# USB_Type-C_Port_V2_0.net
KiCad netlist of a schematic drawn in Altium Designer
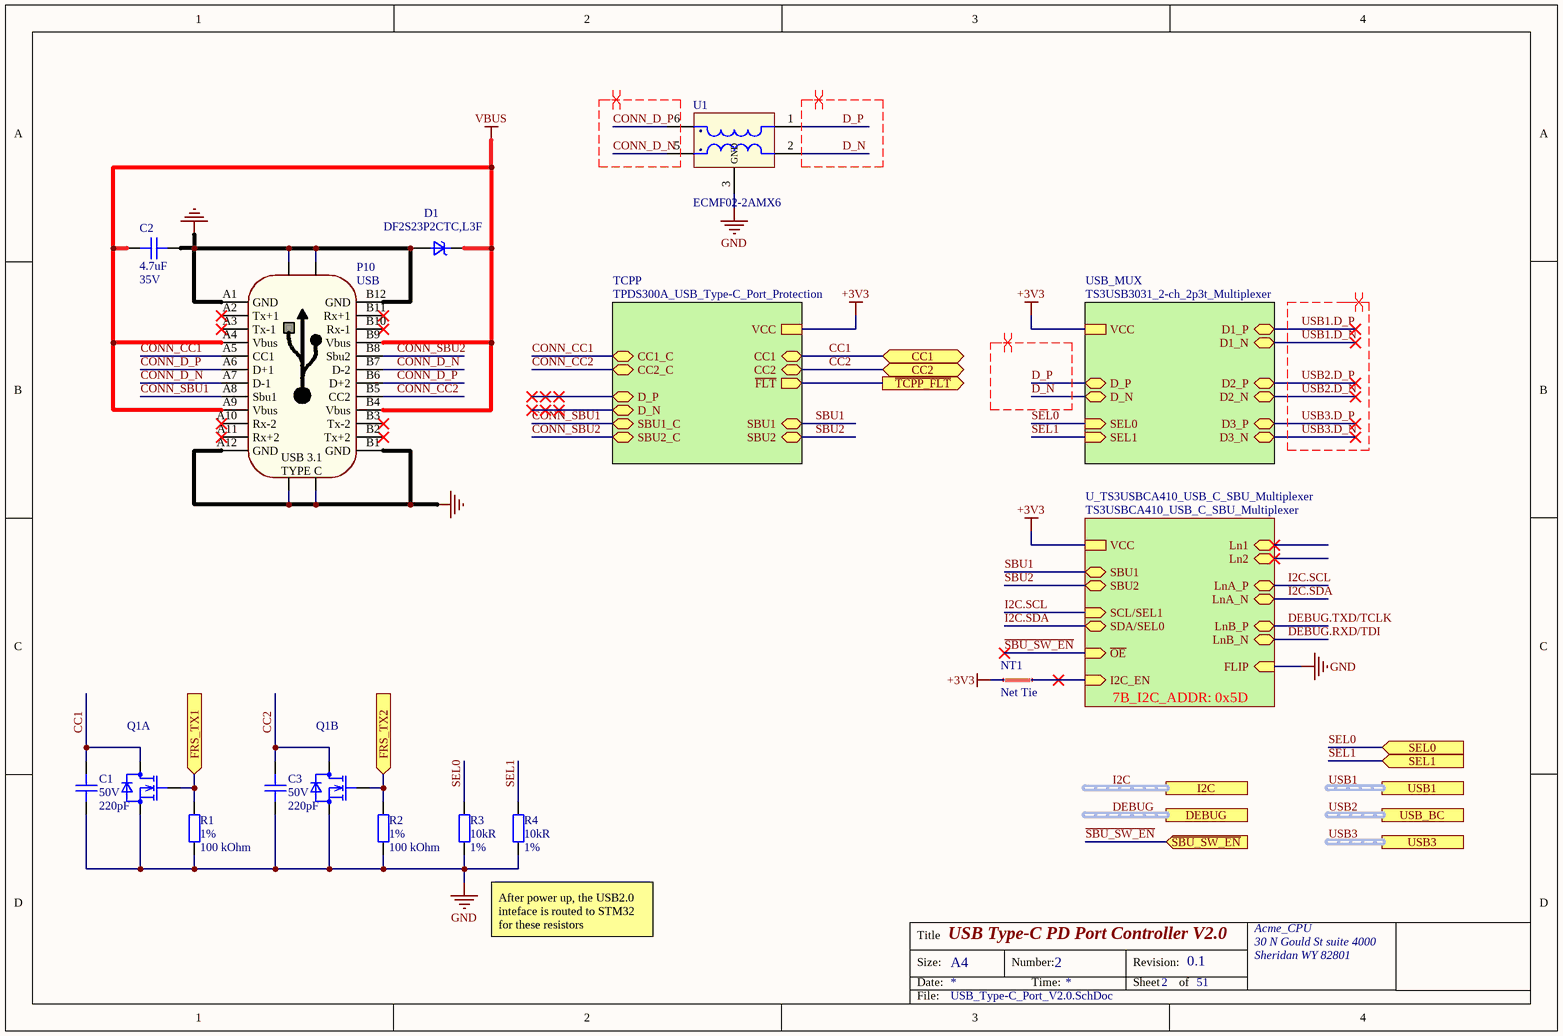
[diagram p0: USB_Type-C_Port_V2.0.SchDoc]

(export (version "E")
  (design (tool "Eeschema 10.0.6"))
  (components
    (comp (ref "C1")
      (value "CAP CER 220PF 50V X7R 0402")
      (footprint "C0402")
      (description "220pF ±10% 50V Ceramic Capacitor X7R 0402 (1005 Metric)")
      (fields
        (field (name "MANUFACTURER") "Yageo")
        (field (name "MANUFACTURER PART NUMBER") "CC0402KRX7R9BB221")
        (field (name "VOLTAGE RATING") "50V")
        (field (name "CAPACITANCE") "220pF")
      )
      (libsource (lib "capacitors_smd") (part "CAP CER 220PF 50V X7R 0402"))
    )
    (comp (ref "C2")
      (value "CAP CER 4.7UF 35V X7R 0805")
      (footprint "C0805")
      (fields
        (field (name "MANUFACTURER") "TDK")
        (field (name "MANUFACTURER PART NUMBER") "C2012X7R1V475K125AC")
        (field (name "TOLERANCE") "10%")
        (field (name "CAPACITANCE") "4.7uF")
        (field (name "VOLTAGE RATING") "35V")
      )
      (libsource (lib "capacitors_smd") (part "CAP CER 4.7UF 35V X7R 0805"))
    )
    (comp (ref "C3")
      (value "CAP CER 220PF 50V X7R 0402")
      (footprint "C0402")
      (description "220pF ±10% 50V Ceramic Capacitor X7R 0402 (1005 Metric)")
      (fields
        (field (name "MANUFACTURER") "Yageo")
        (field (name "MANUFACTURER PART NUMBER") "CC0402KRX7R9BB221")
        (field (name "VOLTAGE RATING") "50V")
        (field (name "CAPACITANCE") "220pF")
      )
      (libsource (lib "capacitors_smd") (part "CAP CER 220PF 50V X7R 0402"))
    )
    (comp (ref "D1")
      (value "DF2S23P2CTC,L3F")
      (footprint "CST2C")
      (description "35.7V Clamp 14A (8/20µs) Ipp Tvs Diode Surface Mount CST2C")
      (fields (field (name "MANUFACTURER") "Toshiba Semiconductor and Storage"))
      (libsource (lib "Control_Board_Model") (part "TVS DIODE 21VWM 35.7VC CST2C"))
    )
    (comp (ref "NT1")
      (value "Net Tie")
      (footprint "Net Tie 6x30mil")
      (libsource (lib "BLDC_Motor_Driver") (part "Net Tie Line"))
    )
    (comp (ref "P10")
      (value "USB")
      (footprint "MOLEX_2012670005")
      (fields (field (name "MANUFACTURER") "Molex") (field (name "MANUFACTURER PART NUMBER") "201267-0005"))
      (libsource (lib "connectors_usb") (part "CONN 2012670005 RCP USB3.1 TYPEC 24P SMD RA"))
    )
    (comp (ref "Q1")
      (value "DMN32D2LV-7")
      (footprint "SON_400UV-7_DIO")
      (description "Mosfet Array 2 N-Channel (Dual) 30V 400mA 400mW Surface Mount SOT-563")
      (fields (field (name "MANUFACTURER") "Diodes"))
      (libsource (lib "mosfets") (part "ARRAY MOSFET 2N-CH 30V 0.4A SOT-563"))
    )
    (comp (ref "R1")
      (value "RES SMD 100K OHM 1% 1/16W 0402")
      (footprint "R0402")
      (description "100 kOhms ±1% 0.063W, 1/16W Chip Resistor 0402 (1005 Metric) Moisture Resistant Thick Film")
      (fields
        (field (name "MANUFACTURER") "Yageo")
        (field (name "MANUFACTURER PART NUMBER") "RC0402FR-07100KL")
        (field (name "TOLERANCE") "1%")
        (field (name "RESISTANCE") "100 kOhm")
      )
      (libsource (lib "resistors_smd") (part "RES SMD 100K OHM 1% 1/16W 0402"))
    )
    (comp (ref "R2")
      (value "RES SMD 100K OHM 1% 1/16W 0402")
      (footprint "R0402")
      (description "100 kOhms ±1% 0.063W, 1/16W Chip Resistor 0402 (1005 Metric) Moisture Resistant Thick Film")
      (fields
        (field (name "MANUFACTURER") "Yageo")
        (field (name "MANUFACTURER PART NUMBER") "RC0402FR-07100KL")
        (field (name "TOLERANCE") "1%")
        (field (name "RESISTANCE") "100 kOhm")
      )
      (libsource (lib "resistors_smd") (part "RES SMD 100K OHM 1% 1/16W 0402"))
    )
    (comp (ref "R3")
      (value "RES SMD 10K OHM 1% 1/16W 0402")
      (footprint "R0402")
      (description "10 kOhms ±1% 0.063W, 1/16W Chip Resistor 0402 (1005 Metric) Moisture Resistant Thick Film")
      (fields
        (field (name "MANUFACTURER") "Yageo")
        (field (name "MANUFACTURER PART NUMBER") "RC0402FR-0710KP")
        (field (name "RESISTANCE") "10kR")
        (field (name "TOLERANCE") "1%")
      )
      (libsource (lib "resistors_smd") (part "RES SMD 10K OHM 1% 1/16W 0402"))
    )
    (comp (ref "R4")
      (value "RES SMD 10K OHM 1% 1/16W 0402")
      (footprint "R0402")
      (description "10 kOhms ±1% 0.063W, 1/16W Chip Resistor 0402 (1005 Metric) Moisture Resistant Thick Film")
      (fields
        (field (name "MANUFACTURER") "Yageo")
        (field (name "MANUFACTURER PART NUMBER") "RC0402FR-0710KP")
        (field (name "RESISTANCE") "10kR")
        (field (name "TOLERANCE") "1%")
      )
      (libsource (lib "resistors_smd") (part "RES SMD 10K OHM 1% 1/16W 0402"))
    )
    (comp (ref "U1")
      (value "ECMF02-2AMX6")
      (footprint "QFN-6L")
      (description "2 Line Common Mode Choke Surface Mount  200mA DCR 2.5Ohm")
      (fields (field (name "MANUFACTURER") "STMicroelectronics"))
      (libsource (lib "diodes_tvs") (part "CMC 200MA 2LN SMD ESD"))
    )
  )
  (nets
    (net (code "6") (name "+3V3") (class "Default") (node (ref "NT1") (pin "1") (pintype "passive")))
    (net (code "7") (name "/CC1") (class "Default")
      (node (ref "C1") (pin "2") (pinfunction "2_2") (pintype "passive"))
      (node (ref "Q1") (pin "6") (pinfunction "D_6") (pintype "passive"))
    )
    (net (code "8") (name "/CC2") (class "Default")
      (node (ref "C3") (pin "2") (pinfunction "2_2") (pintype "passive"))
      (node (ref "Q1") (pin "3") (pinfunction "D_3") (pintype "passive"))
    )
    (net (code "9") (name "/CONN_CC1") (class "Default")
      (node (ref "P10") (pin "A5") (pinfunction "CC1_A5") (pintype "passive"))
    )
    (net (code "10") (name "/CONN_CC2") (class "Default")
      (node (ref "P10") (pin "B5") (pinfunction "CC2_B5") (pintype "passive"))
    )
    (net (code "11") (name "/CONN_D_N") (class "Default")
      (node (ref "P10") (pin "A7") (pinfunction "D-1_A7") (pintype "passive"))
      (node (ref "P10") (pin "B7") (pinfunction "D-2_B7") (pintype "passive"))
      (node (ref "U1") (pin "5") (pinfunction "OUT2_5") (pintype "passive"))
    )
    (net (code "12") (name "/CONN_D_P") (class "Default")
      (node (ref "P10") (pin "A6") (pinfunction "D+1_A6") (pintype "passive"))
      (node (ref "P10") (pin "B6") (pinfunction "D+2_B6") (pintype "passive"))
      (node (ref "U1") (pin "6") (pinfunction "OUT1_6") (pintype "passive"))
    )
    (net (code "13") (name "/CONN_SBU1") (class "Default")
      (node (ref "P10") (pin "A8") (pinfunction "Sbu1_A8") (pintype "passive"))
    )
    (net (code "14") (name "/CONN_SBU2") (class "Default")
      (node (ref "P10") (pin "B8") (pinfunction "Sbu2_B8") (pintype "passive"))
    )
    (net (code "17") (name "/D_N") (class "Default")
      (node (ref "U1") (pin "2") (pinfunction "INP2_2") (pintype "passive"))
    )
    (net (code "19") (name "/D_P") (class "Default")
      (node (ref "U1") (pin "1") (pinfunction "INP1_1") (pintype "passive"))
    )
    (net (code "21") (name "/FRS_TX1") (class "Default")
      (node (ref "Q1") (pin "2") (pinfunction "G_2") (pintype "passive"))
      (node (ref "R1") (pin "2") (pinfunction "2_2") (pintype "passive"))
    )
    (net (code "22") (name "/FRS_TX2") (class "Default")
      (node (ref "Q1") (pin "5") (pinfunction "G_5") (pintype "passive"))
      (node (ref "R2") (pin "2") (pinfunction "2_2") (pintype "passive"))
    )
    (net (code "25") (name "/I2C_EN") (class "Default") (node (ref "NT1") (pin "2") (pintype "passive")))
    (net (code "31") (name "/SEL0") (class "Default")
      (node (ref "R3") (pin "1") (pinfunction "1_1") (pintype "passive"))
    )
    (net (code "32") (name "/SEL1") (class "Default")
      (node (ref "R4") (pin "1") (pinfunction "1_1") (pintype "passive"))
    )
    (net (code "45") (name "GND") (class "Default")
      (node (ref "C1") (pin "1") (pinfunction "1_1") (pintype "passive"))
      (node (ref "C2") (pin "2") (pinfunction "2_2") (pintype "passive"))
      (node (ref "C3") (pin "1") (pinfunction "1_1") (pintype "passive"))
      (node (ref "D1") (pin "2") (pinfunction "A_2") (pintype "passive"))
      (node (ref "P10") (pin "A1") (pinfunction "GND_A1") (pintype "passive"))
      (node (ref "P10") (pin "A12") (pinfunction "GND_A12") (pintype "passive"))
      (node (ref "P10") (pin "B1") (pinfunction "GND_B1") (pintype "passive"))
      (node (ref "P10") (pin "B12") (pinfunction "GND_B12") (pintype "passive"))
      (node (ref "P10") (pin "S1") (pinfunction "S1_S1") (pintype "passive"))
      (node (ref "P10") (pin "S2") (pinfunction "S2_S2") (pintype "passive"))
      (node (ref "P10") (pin "S3") (pinfunction "S3_S3") (pintype "passive"))
      (node (ref "P10") (pin "S4") (pinfunction "S4_S4") (pintype "passive"))
      (node (ref "Q1") (pin "1") (pinfunction "S_1") (pintype "passive"))
      (node (ref "Q1") (pin "4") (pinfunction "S_4") (pintype "passive"))
      (node (ref "R1") (pin "1") (pinfunction "1_1") (pintype "passive"))
      (node (ref "R2") (pin "1") (pinfunction "1_1") (pintype "passive"))
      (node (ref "R3") (pin "2") (pinfunction "2_2") (pintype "passive"))
      (node (ref "R4") (pin "2") (pinfunction "2_2") (pintype "passive"))
      (node (ref "U1") (pin "3") (pinfunction "GND_3") (pintype "power_in"))
    )
    (net (code "46") (name "VBUS") (class "Default")
      (node (ref "C2") (pin "1") (pinfunction "1_1") (pintype "passive"))
      (node (ref "D1") (pin "1") (pinfunction "K_1") (pintype "passive"))
      (node (ref "P10") (pin "A4") (pinfunction "Vbus_A4") (pintype "passive"))
      (node (ref "P10") (pin "A9") (pinfunction "Vbus_A9") (pintype "passive"))
      (node (ref "P10") (pin "B4") (pinfunction "Vbus_B4") (pintype "passive"))
      (node (ref "P10") (pin "B9") (pinfunction "Vbus_B9") (pintype "passive"))
    )
    (net (code "47") (name "unconnected-(P10-Rx+1-PadB11)") (class "Default")
      (node (ref "P10") (pin "B11") (pinfunction "Rx+1_B11") (pintype "passive+no_connect"))
    )
    (net (code "48") (name "unconnected-(P10-Rx+2-PadA11)") (class "Default")
      (node (ref "P10") (pin "A11") (pinfunction "Rx+2_A11") (pintype "passive+no_connect"))
    )
    (net (code "49") (name "unconnected-(P10-Rx-1-PadB10)") (class "Default")
      (node (ref "P10") (pin "B10") (pinfunction "Rx-1_B10") (pintype "passive+no_connect"))
    )
    (net (code "50") (name "unconnected-(P10-Rx-2-PadA10)") (class "Default")
      (node (ref "P10") (pin "A10") (pinfunction "Rx-2_A10") (pintype "passive+no_connect"))
    )
    (net (code "51") (name "unconnected-(P10-Tx+1-PadA2)") (class "Default")
      (node (ref "P10") (pin "A2") (pinfunction "Tx+1_A2") (pintype "passive+no_connect"))
    )
    (net (code "52") (name "unconnected-(P10-Tx+2-PadB2)") (class "Default")
      (node (ref "P10") (pin "B2") (pinfunction "Tx+2_B2") (pintype "passive+no_connect"))
    )
    (net (code "53") (name "unconnected-(P10-Tx-1-PadA3)") (class "Default")
      (node (ref "P10") (pin "A3") (pinfunction "Tx-1_A3") (pintype "passive+no_connect"))
    )
    (net (code "54") (name "unconnected-(P10-Tx-2-PadB3)") (class "Default")
      (node (ref "P10") (pin "B3") (pinfunction "Tx-2_B3") (pintype "passive+no_connect"))
    )
    (net (code "55") (name "unconnected-(U1-NC-Pad4)") (class "Default")
      (node (ref "U1") (pin "4") (pinfunction "NC_4") (pintype "passive"))
    )
  )
)
